# design.net
KiCad netlist of a schematic drawn in Altium Designer
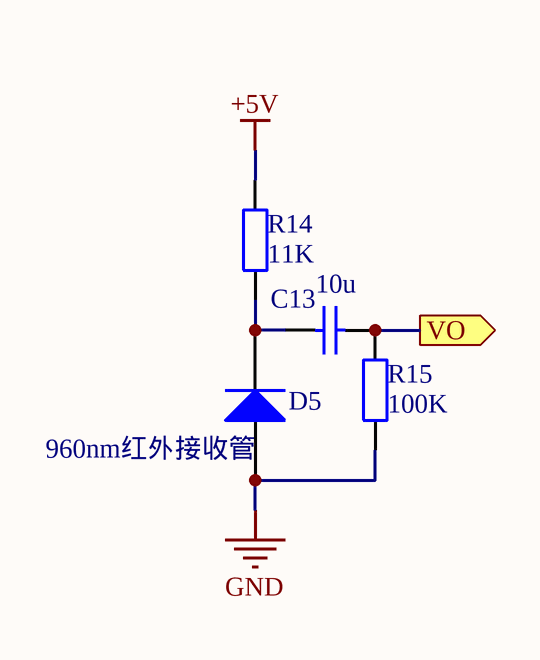
[diagram p0: 红外接收.SchDoc]

(export (version "E")
  (design (tool "Eeschema 10.0.6"))
  (components
    (comp (ref "C13")
      (value "独石电容")
      (footprint "独石电容")
      (fields (field (name "ALTIUM_UNNAMED_1") "10u"))
      (libsource (lib "自制库（原理图文件）") (part "独石电容"))
    )
    (comp (ref "D5")
      (value "960nm红外接收管")
      (footprint "DO-41")
      (description "1 Amp General Purpose Rectifier")
      (fields (field (name "PUBLISHER") "Altium Limited"))
      (libsource (lib "Miscellaneous Devices") (part "Diode 1N4001"))
    )
    (comp (ref "R14")
      (value "11K")
      (footprint "AXIAL-0.4")
      (description "Resistor")
      (fields (field (name "Comment") "Res2") (field (name "PUBLISHER") "Altium Limited"))
      (libsource (lib "Miscellaneous Devices") (part "Res2"))
    )
    (comp (ref "R15")
      (value "100K")
      (footprint "AXIAL-0.4")
      (description "Resistor")
      (fields (field (name "Comment") "Res2") (field (name "PUBLISHER") "Altium Limited"))
      (libsource (lib "Miscellaneous Devices") (part "Res2"))
    )
  )
  (nets
    (net (code "1") (name "+5V") (class "Default")
      (node (ref "R14") (pin "2") (pinfunction "2_2") (pintype "passive"))
    )
    (net (code "2") (name "/VO") (class "Default")
      (node (ref "C13") (pin "2") (pinfunction "2_2") (pintype "passive"))
      (node (ref "R15") (pin "2") (pinfunction "2_2") (pintype "passive"))
    )
    (net (code "3") (name "GND") (class "Default")
      (node (ref "D5") (pin "1") (pinfunction "A_1") (pintype "passive"))
      (node (ref "R15") (pin "1") (pinfunction "1_1") (pintype "passive"))
    )
    (net (code "4") (name "Net-(D5-K)") (class "Default")
      (node (ref "C13") (pin "1") (pinfunction "1_1") (pintype "passive"))
      (node (ref "D5") (pin "2") (pinfunction "K_2") (pintype "passive"))
      (node (ref "R14") (pin "1") (pinfunction "1_1") (pintype "passive"))
    )
  )
)
